# Sheet1.net
KiCad netlist of a schematic drawn in Altium Designer
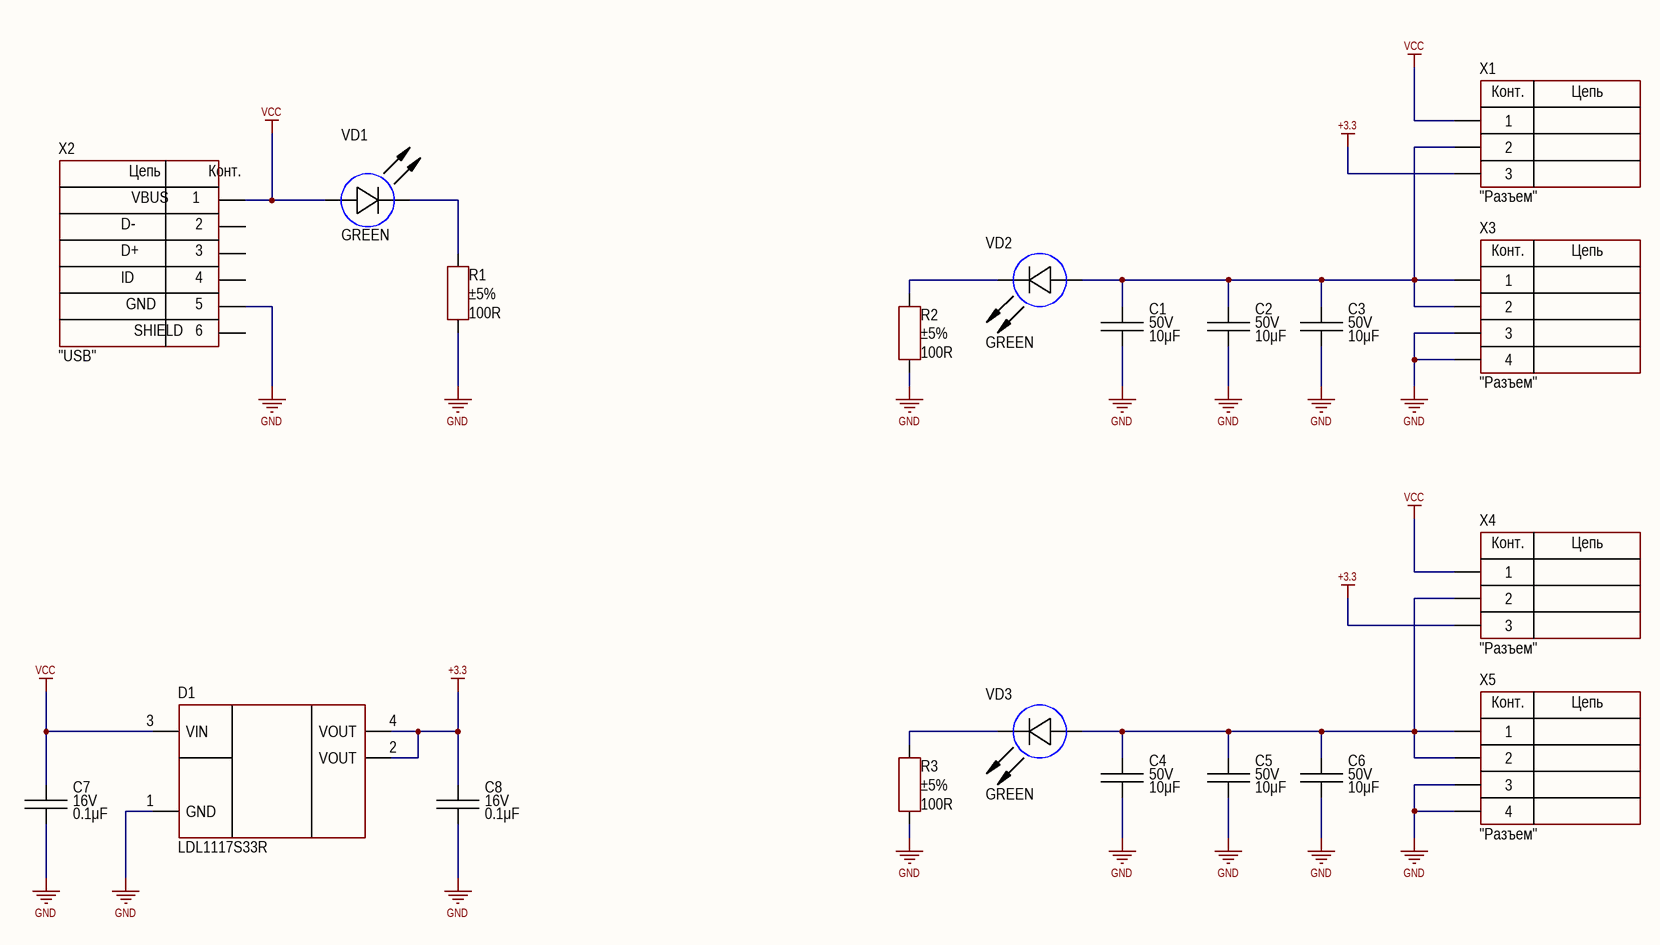
[diagram p0: Sheet1.SchDoc]

(export (version "E")
  (design (tool "Eeschema 10.0.6"))
  (components
    (comp (ref "C1")
      (value "10μF")
      (footprint "CAP: 1206")
      (fields
        (field (name "MANUFACTURER") "Yageo")
        (field (name "PARTNUMBER") "CC1206KRX7R9BB104")
        (field (name "VALUEMANUFACTURERPARTNUMBER") "Ceramic capacitor, 10μF, X7R, ±10%, 50V, 1206, -55...+125°C")
        (field (name "VOLTAGE") "50V")
      )
      (libsource (lib "capacitor") (part "Ceramic_1206"))
    )
    (comp (ref "C2")
      (value "10μF")
      (footprint "CAP: 1206")
      (fields
        (field (name "MANUFACTURER") "Yageo")
        (field (name "PARTNUMBER") "CC1206KRX7R9BB104")
        (field (name "VALUEMANUFACTURERPARTNUMBER") "Ceramic capacitor, 10μF, X7R, ±10%, 50V, 1206, -55...+125°C")
        (field (name "VOLTAGE") "50V")
      )
      (libsource (lib "capacitor") (part "Ceramic_1206"))
    )
    (comp (ref "C3")
      (value "10μF")
      (footprint "CAP: 1206")
      (fields
        (field (name "MANUFACTURER") "Yageo")
        (field (name "PARTNUMBER") "CC1206KRX7R9BB104")
        (field (name "VALUEMANUFACTURERPARTNUMBER") "Ceramic capacitor, 10μF, X7R, ±10%, 50V, 1206, -55...+125°C")
        (field (name "VOLTAGE") "50V")
      )
      (libsource (lib "capacitor") (part "Ceramic_1206"))
    )
    (comp (ref "C4")
      (value "10μF")
      (footprint "CAP: 1206")
      (fields
        (field (name "MANUFACTURER") "Yageo")
        (field (name "PARTNUMBER") "CC1206KRX7R9BB104")
        (field (name "VALUEMANUFACTURERPARTNUMBER") "Ceramic capacitor, 10μF, X7R, ±10%, 50V, 1206, -55...+125°C")
        (field (name "VOLTAGE") "50V")
      )
      (libsource (lib "capacitor") (part "Ceramic_1206"))
    )
    (comp (ref "C5")
      (value "10μF")
      (footprint "CAP: 1206")
      (fields
        (field (name "MANUFACTURER") "Yageo")
        (field (name "PARTNUMBER") "CC1206KRX7R9BB104")
        (field (name "VALUEMANUFACTURERPARTNUMBER") "Ceramic capacitor, 10μF, X7R, ±10%, 50V, 1206, -55...+125°C")
        (field (name "VOLTAGE") "50V")
      )
      (libsource (lib "capacitor") (part "Ceramic_1206"))
    )
    (comp (ref "C6")
      (value "10μF")
      (footprint "CAP: 1206")
      (fields
        (field (name "MANUFACTURER") "Yageo")
        (field (name "PARTNUMBER") "CC1206KRX7R9BB104")
        (field (name "VALUEMANUFACTURERPARTNUMBER") "Ceramic capacitor, 10μF, X7R, ±10%, 50V, 1206, -55...+125°C")
        (field (name "VOLTAGE") "50V")
      )
      (libsource (lib "capacitor") (part "Ceramic_1206"))
    )
    (comp (ref "C7")
      (value "0.1μF")
      (footprint "CAP: 0805")
      (fields
        (field (name "MANUFACTURER") "Yageo")
        (field (name "PARTNUMBER") "CC0805KRX7R7BB104")
        (field (name "VALUEMANUFACTURERPARTNUMBER") "Ceramic capacitor, 0.1μF, X7R, ±10%, 16V, 0805, -55...+125°C")
        (field (name "VOLTAGE") "16V")
      )
      (libsource (lib "capacitor") (part "Ceramic_0805"))
    )
    (comp (ref "C8")
      (value "0.1μF")
      (footprint "CAP: 0805")
      (fields
        (field (name "MANUFACTURER") "Yageo")
        (field (name "PARTNUMBER") "CC0805KRX7R7BB104")
        (field (name "VALUEMANUFACTURERPARTNUMBER") "Ceramic capacitor, 0.1μF, X7R, ±10%, 16V, 0805, -55...+125°C")
        (field (name "VOLTAGE") "16V")
      )
      (libsource (lib "capacitor") (part "Ceramic_0805"))
    )
    (comp (ref "D1")
      (value "~")
      (footprint "SOT223")
      (description "Linear voltage regulator")
      (fields
        (field (name "MANUFACTURER") "STMicroelectronics")
        (field (name "VALUEMANUFACTURERPARTNUMBER") "Linear voltage regulator, input 3.9...18V, 0.6V, output 3.3V, 1.2A, -40...+85°C, SOT223")
        (field (name "PARTNUMBER") "LDL1117S33R")
      )
      (libsource (lib "ic-power-supply") (part "LDL1117S33R"))
    )
    (comp (ref "R1")
      (value "100R")
      (footprint "RES: 0603")
      (fields
        (field (name "MANUFACTURER") "Yageo")
        (field (name "PARTNUMBER") "RC0603JR-07100RL")
        (field (name "VALUEMANUFACTURERPARTNUMBER") "Resistor film, 100R, ±5%, 0603, 0.1W, -55...+125°C")
        (field (name "TOLERANCE") "±5%")
      )
      (libsource (lib "") (part "Resistor_0603_1"))
    )
    (comp (ref "R2")
      (value "100R")
      (footprint "RES: 0603")
      (fields
        (field (name "MANUFACTURER") "Yageo")
        (field (name "PARTNUMBER") "RC0603JR-07100RL")
        (field (name "VALUEMANUFACTURERPARTNUMBER") "Resistor film, 100R, ±5%, 0603, 0.1W, -55...+125°C")
        (field (name "TOLERANCE") "±5%")
      )
      (libsource (lib "resistor") (part "Resistor_0603"))
    )
    (comp (ref "R3")
      (value "100R")
      (footprint "RES: 0603")
      (fields
        (field (name "MANUFACTURER") "Yageo")
        (field (name "PARTNUMBER") "RC0603JR-07100RL")
        (field (name "VALUEMANUFACTURERPARTNUMBER") "Resistor film, 100R, ±5%, 0603, 0.1W, -55...+125°C")
        (field (name "TOLERANCE") "±5%")
      )
      (libsource (lib "resistor") (part "Resistor_0603"))
    )
    (comp (ref "VD1")
      (value "~")
      (footprint "LED: 0603R")
      (fields
        (field (name "VALUEMANUFACTURERPARTNUMBER") "LED, Green, *, *, *, -55...+150°C")
        (field (name "COLOR") "GREEN")
      )
      (libsource (lib "diode") (part "LED_single"))
    )
    (comp (ref "VD2")
      (value "~")
      (footprint "LED: 0603R")
      (fields
        (field (name "VALUEMANUFACTURERPARTNUMBER") "LED, Green, *, *, *, -55...+150°C")
        (field (name "COLOR") "GREEN")
      )
      (libsource (lib "diode") (part "LED_single"))
    )
    (comp (ref "VD3")
      (value "~")
      (footprint "LED: 0603R")
      (fields
        (field (name "VALUEMANUFACTURERPARTNUMBER") "LED, Green, *, *, *, -55...+150°C")
        (field (name "COLOR") "GREEN")
      )
      (libsource (lib "diode") (part "LED_single"))
    )
    (comp (ref "X1")
      (value "~")
      (footprint "CON: PLS-3")
      (fields
        (field (name "MANUFACTURER") "Connfly")
        (field (name "VALUEMANUFACTURERPARTNUMBER") "Connector, 3pin, 2.54mm, 500VAC, 3A")
        (field (name "PARTNUMBER") "PLS-3")
        (field (name "COMMENTTEXT") "\"Разъем\"")
      )
      (libsource (lib "connector") (part "PLS-3"))
    )
    (comp (ref "X2")
      (value "~")
      (footprint "CON: USB micro-A (ZX62-B-5PA)")
      (fields
        (field (name "MANUFACTURER") "Hirose Electric")
        (field (name "VALUEMANUFACTURERPARTNUMBER") "USB micro B")
        (field (name "PARTNUMBER") "ZX62-B-5PA")
        (field (name "COMMENTTEXT") "\"USB\"")
      )
      (libsource (lib "connector") (part "Connector_USB_micro_B"))
    )
    (comp (ref "X3")
      (value "~")
      (footprint "CON: PLD-4")
      (fields
        (field (name "MANUFACTURER") "Connfly")
        (field (name "VALUEMANUFACTURERPARTNUMBER") "Connector, 6pin, 2.54mm, 500VAC, 3A")
        (field (name "PARTNUMBER") "PLD-4")
        (field (name "COMMENTTEXT") "\"Разъем\"")
      )
      (libsource (lib "connector") (part "PLD-4"))
    )
    (comp (ref "X4")
      (value "~")
      (footprint "CON: PLS-3")
      (fields
        (field (name "MANUFACTURER") "Connfly")
        (field (name "VALUEMANUFACTURERPARTNUMBER") "Connector, 3pin, 2.54mm, 500VAC, 3A")
        (field (name "PARTNUMBER") "PLS-3")
        (field (name "COMMENTTEXT") "\"Разъем\"")
      )
      (libsource (lib "connector") (part "PLS-3"))
    )
    (comp (ref "X5")
      (value "~")
      (footprint "CON: PLD-4")
      (fields
        (field (name "MANUFACTURER") "Connfly")
        (field (name "VALUEMANUFACTURERPARTNUMBER") "Connector, 6pin, 2.54mm, 500VAC, 3A")
        (field (name "PARTNUMBER") "PLD-4")
        (field (name "COMMENTTEXT") "\"Разъем\"")
      )
      (libsource (lib "connector") (part "PLD-4"))
    )
  )
  (nets
    (net (code "1") (name "+3.3") (class "Default")
      (node (ref "C8") (pin "1") (pinfunction "1_1") (pintype "passive"))
      (node (ref "D1") (pin "2") (pinfunction "VOUT_2") (pintype "power_in"))
      (node (ref "D1") (pin "4") (pinfunction "VOUT_4") (pintype "power_in"))
      (node (ref "X1") (pin "3") (pinfunction "3_3") (pintype "power_in"))
      (node (ref "X4") (pin "3") (pinfunction "3_3") (pintype "power_in"))
    )
    (net (code "2") (name "GND") (class "Default")
      (node (ref "C1") (pin "1") (pinfunction "1_1") (pintype "passive"))
      (node (ref "C2") (pin "1") (pinfunction "1_1") (pintype "passive"))
      (node (ref "C3") (pin "1") (pinfunction "1_1") (pintype "passive"))
      (node (ref "C4") (pin "1") (pinfunction "1_1") (pintype "passive"))
      (node (ref "C5") (pin "1") (pinfunction "1_1") (pintype "passive"))
      (node (ref "C6") (pin "1") (pinfunction "1_1") (pintype "passive"))
      (node (ref "C7") (pin "2") (pinfunction "2_2") (pintype "passive"))
      (node (ref "C8") (pin "2") (pinfunction "2_2") (pintype "passive"))
      (node (ref "D1") (pin "1") (pinfunction "GND_1") (pintype "power_in"))
      (node (ref "R1") (pin "1") (pinfunction "1_1") (pintype "passive"))
      (node (ref "R2") (pin "2") (pinfunction "2_2") (pintype "passive"))
      (node (ref "R3") (pin "2") (pinfunction "2_2") (pintype "passive"))
      (node (ref "X2") (pin "5") (pinfunction "5_5") (pintype "passive"))
      (node (ref "X3") (pin "3") (pinfunction "3_3") (pintype "power_in"))
      (node (ref "X3") (pin "4") (pinfunction "4_4") (pintype "power_in"))
      (node (ref "X5") (pin "3") (pinfunction "3_3") (pintype "power_in"))
      (node (ref "X5") (pin "4") (pinfunction "4_4") (pintype "power_in"))
    )
    (net (code "3") (name "Net-(VD1-C)") (class "Default")
      (node (ref "R1") (pin "2") (pinfunction "2_2") (pintype "passive"))
      (node (ref "VD1") (pin "2") (pinfunction "C_2") (pintype "passive"))
    )
    (net (code "4") (name "Net-(VD2-A)") (class "Default")
      (node (ref "C1") (pin "2") (pinfunction "2_2") (pintype "passive"))
      (node (ref "C2") (pin "2") (pinfunction "2_2") (pintype "passive"))
      (node (ref "C3") (pin "2") (pinfunction "2_2") (pintype "passive"))
      (node (ref "VD2") (pin "1") (pinfunction "A_1") (pintype "passive"))
      (node (ref "X1") (pin "2") (pinfunction "2_2") (pintype "passive"))
      (node (ref "X3") (pin "1") (pinfunction "1_1") (pintype "passive"))
      (node (ref "X3") (pin "2") (pinfunction "2_2") (pintype "passive"))
    )
    (net (code "5") (name "Net-(VD2-C)") (class "Default")
      (node (ref "R2") (pin "1") (pinfunction "1_1") (pintype "passive"))
      (node (ref "VD2") (pin "2") (pinfunction "C_2") (pintype "passive"))
    )
    (net (code "6") (name "Net-(VD3-A)") (class "Default")
      (node (ref "C4") (pin "2") (pinfunction "2_2") (pintype "passive"))
      (node (ref "C5") (pin "2") (pinfunction "2_2") (pintype "passive"))
      (node (ref "C6") (pin "2") (pinfunction "2_2") (pintype "passive"))
      (node (ref "VD3") (pin "1") (pinfunction "A_1") (pintype "passive"))
      (node (ref "X4") (pin "2") (pinfunction "2_2") (pintype "passive"))
      (node (ref "X5") (pin "1") (pinfunction "1_1") (pintype "passive"))
      (node (ref "X5") (pin "2") (pinfunction "2_2") (pintype "passive"))
    )
    (net (code "7") (name "Net-(VD3-C)") (class "Default")
      (node (ref "R3") (pin "1") (pinfunction "1_1") (pintype "passive"))
      (node (ref "VD3") (pin "2") (pinfunction "C_2") (pintype "passive"))
    )
    (net (code "8") (name "VCC") (class "Default")
      (node (ref "C7") (pin "1") (pinfunction "1_1") (pintype "passive"))
      (node (ref "D1") (pin "3") (pinfunction "VIN_3") (pintype "power_in"))
      (node (ref "VD1") (pin "1") (pinfunction "A_1") (pintype "passive"))
      (node (ref "X1") (pin "1") (pinfunction "1_1") (pintype "passive"))
      (node (ref "X2") (pin "1") (pintype "passive"))
      (node (ref "X4") (pin "1") (pinfunction "1_1") (pintype "passive"))
    )
    (net (code "9") (name "unconnected-(X2-Pad0)") (class "Default")
      (node (ref "X2") (pin "0") (pinfunction "0_0") (pintype "passive"))
    )
    (net (code "10") (name "unconnected-(X2-Pad2)") (class "Default")
      (node (ref "X2") (pin "2") (pinfunction "2_2") (pintype "passive"))
    )
    (net (code "11") (name "unconnected-(X2-Pad3)") (class "Default")
      (node (ref "X2") (pin "3") (pinfunction "3_3") (pintype "passive"))
    )
    (net (code "12") (name "unconnected-(X2-Pad4)") (class "Default")
      (node (ref "X2") (pin "4") (pinfunction "4_4") (pintype "passive"))
    )
  )
)
